# OpenBLC_MCP73831.net
KiCad netlist of a schematic drawn in Altium Designer
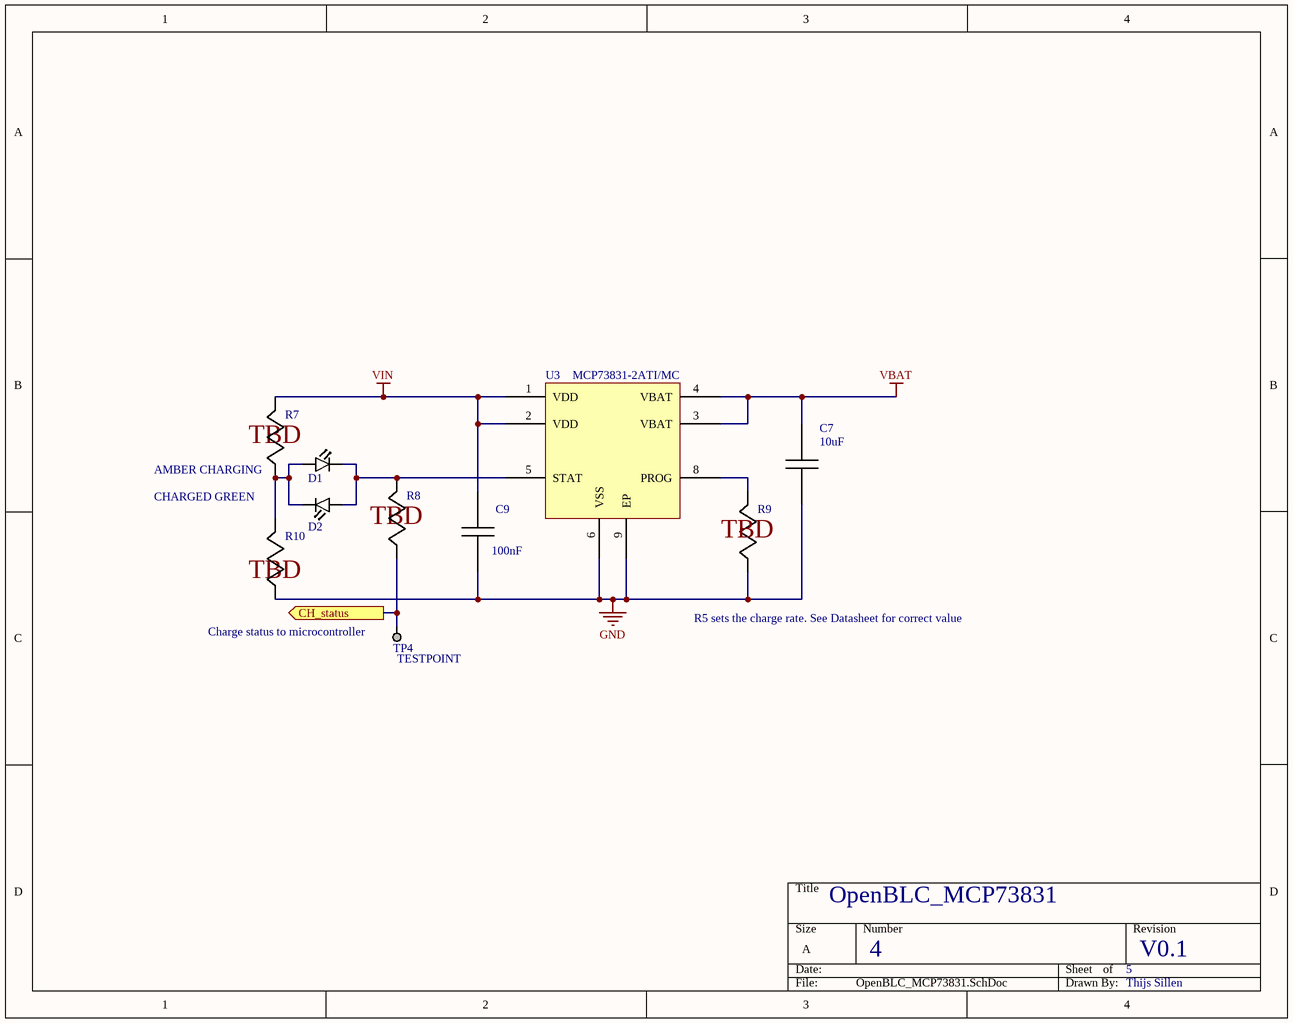
[diagram p0: OpenBLC_MCP73831.SchDoc]

(export (version "E")
  (design (tool "Eeschema 10.0.6"))
  (components
    (comp (ref "C7")
      (value "GRM21BR61A106KE19L")
      (footprint "0805_CAP")
      (description "MURATA - GRM21BR61A106KE19L - CAPACITOR, CERA, 10UF, 10%, 10V, 10%, SMD")
      (fields (field (name "MANUFACTURER") "MURATA") (field (name "CAPACITANCE") "10uF"))
      (libsource (lib "Schlib1") (part "GRM21BR61A106KE19L"))
    )
    (comp (ref "C9")
      (value "0805_CAP")
      (footprint "0805_CAP")
      (fields (field (name "=VALUE") "100nF"))
      (libsource (lib "Schlib1") (part "0805_CAP"))
    )
    (comp (ref "D1")
      (value "0603LED_YE")
      (footprint "0603 _DIODE_YE")
      (libsource (lib "Schlib1") (part "0603LED_YE"))
    )
    (comp (ref "D2")
      (value "0603LED_GR")
      (footprint "0603 _DIODE_GR")
      (libsource (lib "Schlib1") (part "0603LED_GR"))
    )
    (comp (ref "R7") (value "0805_RES") (footprint "0805_RES") (libsource (lib "Schlib1") (part "0805_RES")))
    (comp (ref "R8") (value "0805_RES") (footprint "0805_RES") (libsource (lib "Schlib1") (part "0805_RES")))
    (comp (ref "R9") (value "0805_RES") (footprint "0805_RES") (libsource (lib "Schlib1") (part "0805_RES")))
    (comp (ref "R10") (value "0805_RES") (footprint "0805_RES") (libsource (lib "Schlib1") (part "0805_RES")))
    (comp (ref "TP4")
      (value "TESTPOINT")
      (footprint "Via_TP")
      (description "TESTPOINT SCOPE GRABBER")
      (fields
        (field (name "MANUFACTURER PART NUMBER") "5010")
        (field (name "MANUFACTURER") "Keystone Electronics")
      )
      (libsource (lib "vh_altium_library") (part "TESTPOINT"))
    )
    (comp (ref "U3")
      (value "MCP73831-2ATI/MC")
      (footprint "PQFN50P300X200X5_HS-9N")
      (description "Batterijbeheer Li-Ion/Li-Poly Charg Mgnt 4.2V Vreg out")
      (fields
        (field (name "MANUFACTURER") "Microchip Technology")
        (field (name "MANUFACTURER PART NUMBER") "MCP73831-2ATI/MC")
      )
      (libsource (lib "Schlib1") (part "MCP73831-2ATI/MC"))
    )
  )
  (nets
    (net (code "1") (name "/CH_status") (class "Default")
      (node (ref "R8") (pin "2") (pinfunction "2_2") (pintype "passive"))
      (node (ref "TP4") (pin "1") (pinfunction "1_1") (pintype "passive"))
    )
    (net (code "2") (name "GND") (class "Default")
      (node (ref "C7") (pin "2") (pinfunction "2_2") (pintype "passive"))
      (node (ref "C9") (pin "2") (pinfunction "2_2") (pintype "passive"))
      (node (ref "R10") (pin "2") (pinfunction "2_2") (pintype "passive"))
      (node (ref "R9") (pin "2") (pinfunction "2_2") (pintype "passive"))
      (node (ref "U3") (pin "6") (pinfunction "VSS_6") (pintype "passive"))
      (node (ref "U3") (pin "9") (pinfunction "EP_9") (pintype "passive"))
    )
    (net (code "3") (name "Net-(D1-Pad2)") (class "Default")
      (node (ref "D1") (pin "2") (pinfunction "2_2") (pintype "passive"))
      (node (ref "D2") (pin "1") (pinfunction "1_1") (pintype "passive"))
      (node (ref "R10") (pin "1") (pinfunction "1_1") (pintype "passive"))
      (node (ref "R7") (pin "2") (pinfunction "2_2") (pintype "passive"))
    )
    (net (code "4") (name "Net-(U3-PROG)") (class "Default")
      (node (ref "R9") (pin "1") (pinfunction "1_1") (pintype "passive"))
      (node (ref "U3") (pin "8") (pinfunction "PROG_8") (pintype "passive"))
    )
    (net (code "5") (name "Net-(U3-STAT)") (class "Default")
      (node (ref "D1") (pin "1") (pinfunction "1_1") (pintype "passive"))
      (node (ref "D2") (pin "2") (pinfunction "2_2") (pintype "passive"))
      (node (ref "R8") (pin "1") (pinfunction "1_1") (pintype "passive"))
      (node (ref "U3") (pin "5") (pinfunction "STAT_5") (pintype "passive"))
    )
    (net (code "6") (name "VBAT") (class "Default")
      (node (ref "C7") (pin "1") (pinfunction "1_1") (pintype "passive"))
      (node (ref "U3") (pin "3") (pinfunction "VBAT_3") (pintype "passive"))
      (node (ref "U3") (pin "4") (pinfunction "VBAT_4") (pintype "passive"))
    )
    (net (code "7") (name "VIN") (class "Default")
      (node (ref "C9") (pin "1") (pinfunction "1_1") (pintype "passive"))
      (node (ref "R7") (pin "1") (pinfunction "1_1") (pintype "passive"))
      (node (ref "U3") (pin "1") (pinfunction "VDD_1") (pintype "passive"))
      (node (ref "U3") (pin "2") (pinfunction "VDD_2") (pintype "passive"))
    )
  )
)
